# oresat-camera-board-v2.net
KiCad netlist of a schematic drawn in EAGLE
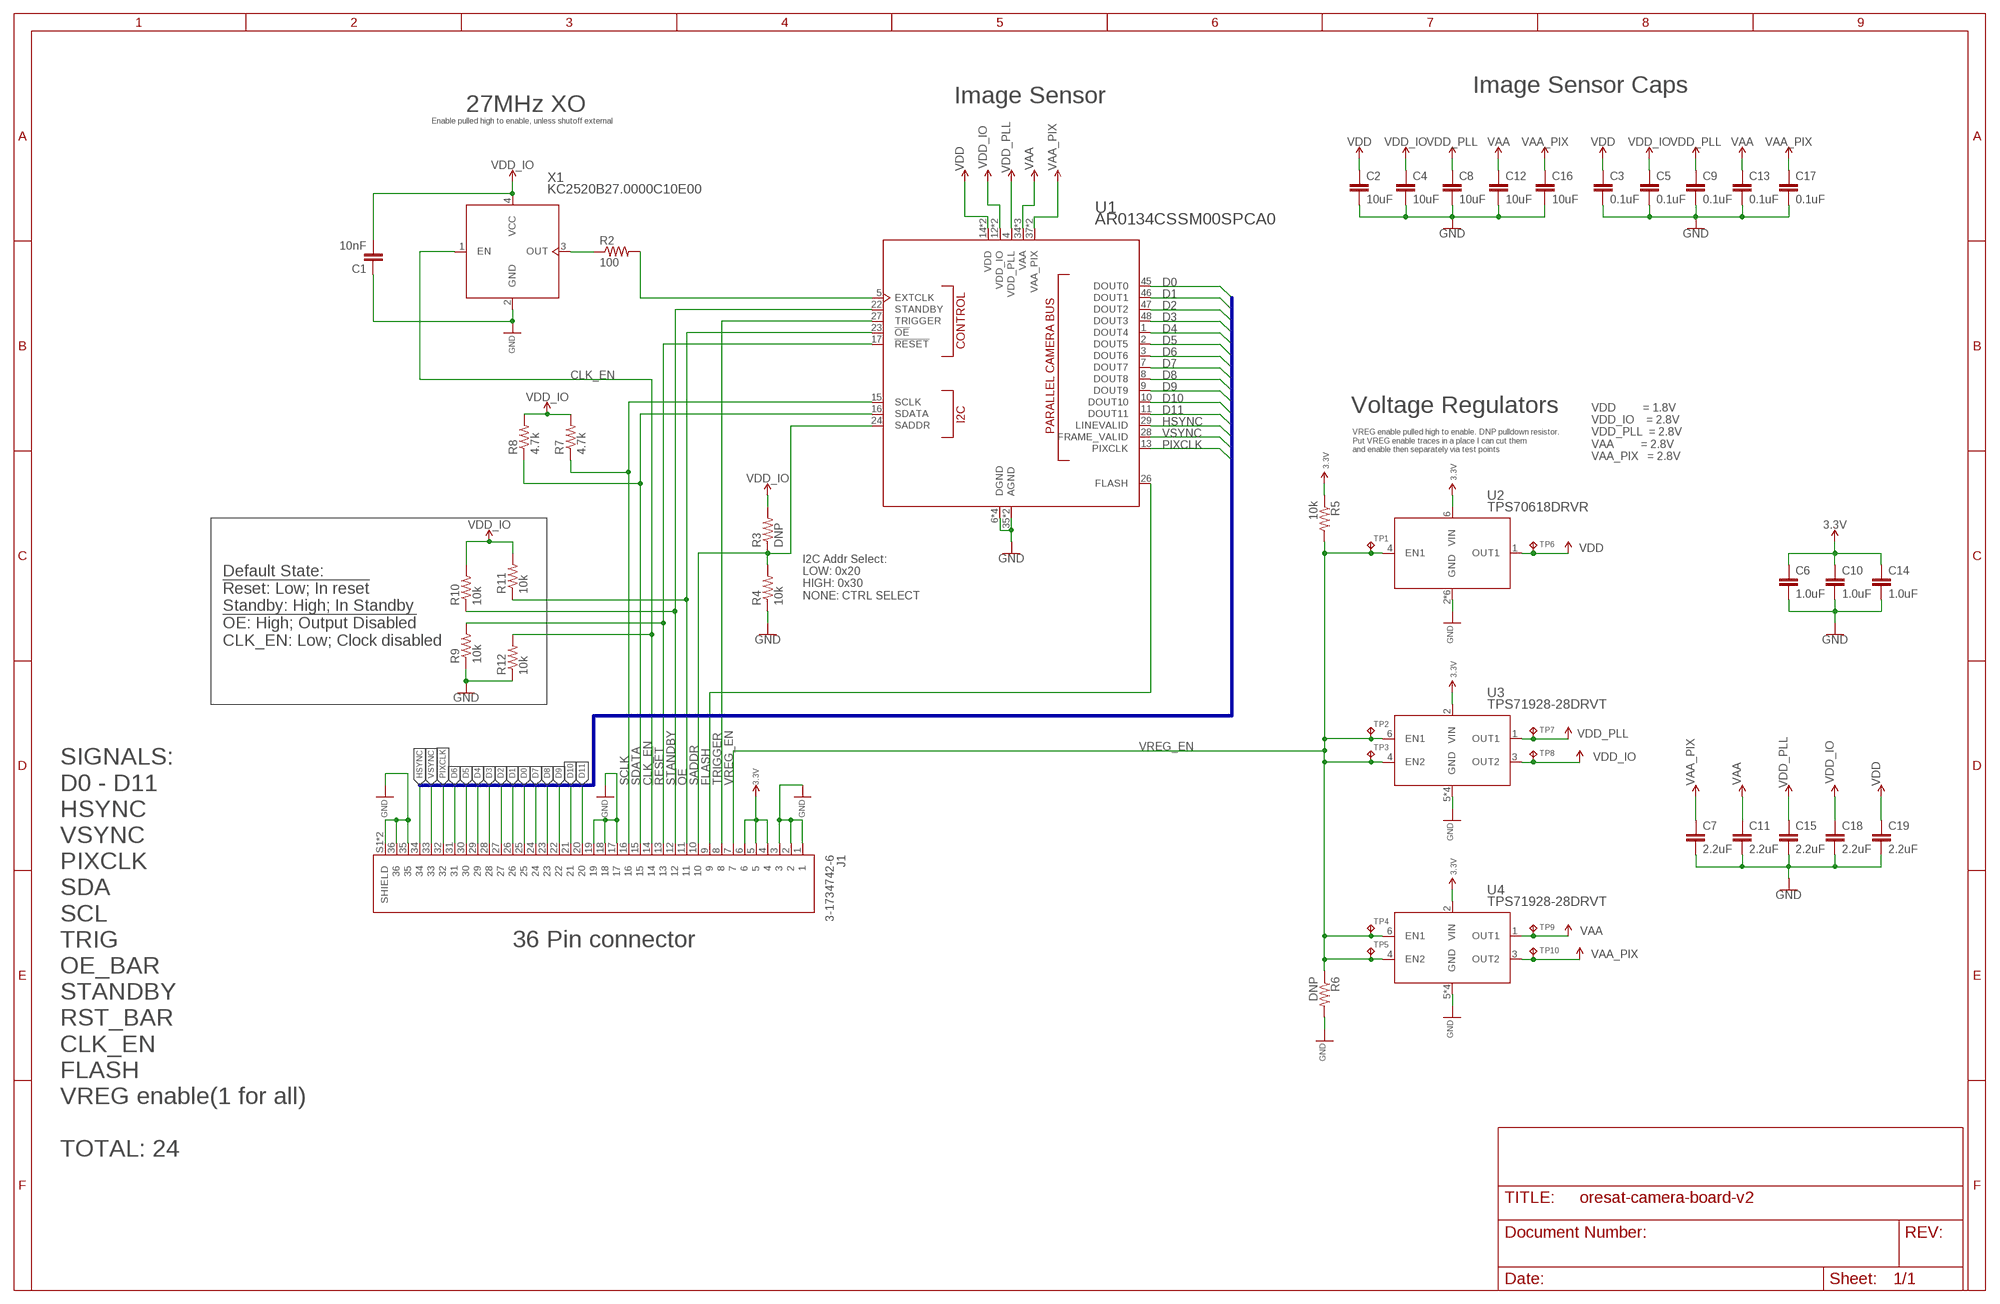
[diagram p0: schematic, sheet 1]

(export (version "E")
  (design (tool "Eeschema 10.0.6"))
  (components
    (comp (ref "C1")
      (value "10nF")
      (footprint "eagle-import:.0402-A-NOSILK")
      (libsource (lib "eagle-import") (part "C-EU0402-A-NOSILK"))
    )
    (comp (ref "C2")
      (value "10uF")
      (footprint "eagle-import:.0603-C-NOSILK")
      (libsource (lib "eagle-import") (part "C-EU0603-C-NOSILK"))
    )
    (comp (ref "C3")
      (value "0.1uF")
      (footprint "eagle-import:.0402-B-NOSILK")
      (libsource (lib "eagle-import") (part "C-EU0402-B-NOSILK"))
    )
    (comp (ref "C4")
      (value "10uF")
      (footprint "eagle-import:.0603-C-NOSILK")
      (libsource (lib "eagle-import") (part "C-EU0603-C-NOSILK"))
    )
    (comp (ref "C5")
      (value "0.1uF")
      (footprint "eagle-import:.0402-B-NOSILK")
      (libsource (lib "eagle-import") (part "C-EU0402-B-NOSILK"))
    )
    (comp (ref "C6")
      (value "1.0uF")
      (footprint "eagle-import:.0603-C-NOSILK")
      (libsource (lib "eagle-import") (part "C-EU0603-C-NOSILK"))
    )
    (comp (ref "C7")
      (value "2.2uF")
      (footprint "eagle-import:.0603-C-NOSILK")
      (libsource (lib "eagle-import") (part "C-EU0603-C-NOSILK"))
    )
    (comp (ref "C8")
      (value "10uF")
      (footprint "eagle-import:.0603-C-NOSILK")
      (libsource (lib "eagle-import") (part "C-EU0603-C-NOSILK"))
    )
    (comp (ref "C9")
      (value "0.1uF")
      (footprint "eagle-import:.0402-B-NOSILK")
      (libsource (lib "eagle-import") (part "C-EU0402-B-NOSILK"))
    )
    (comp (ref "C10")
      (value "1.0uF")
      (footprint "eagle-import:.0603-C-NOSILK")
      (libsource (lib "eagle-import") (part "C-EU0603-C-NOSILK"))
    )
    (comp (ref "C11")
      (value "2.2uF")
      (footprint "eagle-import:.0603-C-NOSILK")
      (libsource (lib "eagle-import") (part "C-EU0603-C-NOSILK"))
    )
    (comp (ref "C12")
      (value "10uF")
      (footprint "eagle-import:.0603-C-NOSILK")
      (libsource (lib "eagle-import") (part "C-EU0603-C-NOSILK"))
    )
    (comp (ref "C13")
      (value "0.1uF")
      (footprint "eagle-import:.0402-B-NOSILK")
      (libsource (lib "eagle-import") (part "C-EU0402-B-NOSILK"))
    )
    (comp (ref "C14")
      (value "1.0uF")
      (footprint "eagle-import:.0603-C-NOSILK")
      (libsource (lib "eagle-import") (part "C-EU0603-C-NOSILK"))
    )
    (comp (ref "C15")
      (value "2.2uF")
      (footprint "eagle-import:.0603-C-NOSILK")
      (libsource (lib "eagle-import") (part "C-EU0603-C-NOSILK"))
    )
    (comp (ref "C16")
      (value "10uF")
      (footprint "eagle-import:.0603-C-NOSILK")
      (libsource (lib "eagle-import") (part "C-EU0603-C-NOSILK"))
    )
    (comp (ref "C17")
      (value "0.1uF")
      (footprint "eagle-import:.0402-B-NOSILK")
      (libsource (lib "eagle-import") (part "C-EU0402-B-NOSILK"))
    )
    (comp (ref "C18")
      (value "2.2uF")
      (footprint "eagle-import:.0603-C-NOSILK")
      (libsource (lib "eagle-import") (part "C-EU0603-C-NOSILK"))
    )
    (comp (ref "C19")
      (value "2.2uF")
      (footprint "eagle-import:.0603-C-NOSILK")
      (libsource (lib "eagle-import") (part "C-EU0603-C-NOSILK"))
    )
    (comp (ref "J1")
      (value "3-1734742-6")
      (footprint "eagle-import:TE_3-1734742-6")
      (fields
        (field (name "COMMENT") "4-1734742-0")
        (field (name "DIGI-KEY_PART_NUMBER") "A100242CT-ND")
        (field (name "MF") "TE Connectivity")
      )
      (libsource (lib "eagle-import") (part "3-1734742-6"))
    )
    (comp (ref "R2")
      (value "100")
      (footprint "eagle-import:.0402-B")
      (libsource (lib "eagle-import") (part "R-US_0402-B"))
    )
    (comp (ref "R3")
      (value "DNP")
      (footprint "eagle-import:.0402-B-NOSILK")
      (libsource (lib "eagle-import") (part "R-US_0402-B-NOSILK"))
    )
    (comp (ref "R4")
      (value "10k")
      (footprint "eagle-import:.0402-B-NOSILK")
      (libsource (lib "eagle-import") (part "R-US_0402-B-NOSILK"))
    )
    (comp (ref "R5")
      (value "10k")
      (footprint "eagle-import:.0402-B-NOSILK")
      (libsource (lib "eagle-import") (part "R-US_0402-B-NOSILK"))
    )
    (comp (ref "R6")
      (value "DNP")
      (footprint "eagle-import:.0402-B-NOSILK")
      (libsource (lib "eagle-import") (part "R-US_0402-B-NOSILK"))
    )
    (comp (ref "R7")
      (value "4.7k")
      (footprint "eagle-import:.0402-B-NOSILK")
      (libsource (lib "eagle-import") (part "R-US_0402-B-NOSILK"))
    )
    (comp (ref "R8")
      (value "4.7k")
      (footprint "eagle-import:.0402-B-NOSILK")
      (libsource (lib "eagle-import") (part "R-US_0402-B-NOSILK"))
    )
    (comp (ref "R9")
      (value "10k")
      (footprint "eagle-import:.0402-B")
      (libsource (lib "eagle-import") (part "R-US_0402-B"))
    )
    (comp (ref "R10")
      (value "10k")
      (footprint "eagle-import:.0402-B")
      (libsource (lib "eagle-import") (part "R-US_0402-B"))
    )
    (comp (ref "R11")
      (value "10k")
      (footprint "eagle-import:.0402-B")
      (libsource (lib "eagle-import") (part "R-US_0402-B"))
    )
    (comp (ref "R12")
      (value "10k")
      (footprint "eagle-import:.0402-B")
      (libsource (lib "eagle-import") (part "R-US_0402-B"))
    )
    (comp (ref "TP1")
      (value "TPTP06R")
      (footprint "eagle-import:TP06R")
      (libsource (lib "eagle-import") (part "TPTP06R"))
    )
    (comp (ref "TP2")
      (value "TPTP06R")
      (footprint "eagle-import:TP06R")
      (libsource (lib "eagle-import") (part "TPTP06R"))
    )
    (comp (ref "TP3")
      (value "TPTP06R")
      (footprint "eagle-import:TP06R")
      (libsource (lib "eagle-import") (part "TPTP06R"))
    )
    (comp (ref "TP4")
      (value "TPTP06R")
      (footprint "eagle-import:TP06R")
      (libsource (lib "eagle-import") (part "TPTP06R"))
    )
    (comp (ref "TP5")
      (value "TPTP06R")
      (footprint "eagle-import:TP06R")
      (libsource (lib "eagle-import") (part "TPTP06R"))
    )
    (comp (ref "TP6")
      (value "TPTP06R")
      (footprint "eagle-import:TP06R")
      (libsource (lib "eagle-import") (part "TPTP06R"))
    )
    (comp (ref "TP7")
      (value "TPTP06R")
      (footprint "eagle-import:TP06R")
      (libsource (lib "eagle-import") (part "TPTP06R"))
    )
    (comp (ref "TP8")
      (value "TPTP06R")
      (footprint "eagle-import:TP06R")
      (libsource (lib "eagle-import") (part "TPTP06R"))
    )
    (comp (ref "TP9")
      (value "TPTP06R")
      (footprint "eagle-import:TP06R")
      (libsource (lib "eagle-import") (part "TPTP06R"))
    )
    (comp (ref "TP10")
      (value "TPTP06R")
      (footprint "eagle-import:TP06R")
      (libsource (lib "eagle-import") (part "TPTP06R"))
    )
    (comp (ref "U1")
      (value "AR0134CSSM00SPCA0")
      (footprint "eagle-import:AR0134CSSM00SPCA0")
      (libsource (lib "eagle-import") (part "AR0134CSSM00SPCA0"))
    )
    (comp (ref "U2")
      (value "TPS70618DRVR")
      (footprint "eagle-import:DRV6_1P6X1")
      (fields (field (name "MANUFACTURER_PART_NUMBER") "TPS7192828DRVT"))
      (libsource (lib "eagle-import") (part "TPS70618DRVR"))
    )
    (comp (ref "U3")
      (value "TPS71928-28DRVT")
      (footprint "eagle-import:DRV6_1P6X1")
      (fields (field (name "MANUFACTURER_PART_NUMBER") "TPS7192828DRVT"))
      (libsource (lib "eagle-import") (part "TPS71928-28DRVT"))
    )
    (comp (ref "U4")
      (value "TPS71928-28DRVT")
      (footprint "eagle-import:DRV6_1P6X1")
      (fields (field (name "MANUFACTURER_PART_NUMBER") "TPS7192828DRVT"))
      (libsource (lib "eagle-import") (part "TPS71928-28DRVT"))
    )
    (comp (ref "X1")
      (value "KC2520B27.0000C10E00")
      (footprint "eagle-import:OSC_KYOCERA_KC2520B")
      (libsource (lib "eagle-import") (part "KC2520B27.0000C10E00"))
    )
  )
  (nets
    (net (code "1") (name "/CLK_EN") (class "Default")
      (node (ref "J1") (pin "14") (pinfunction "14_14") (pintype "passive"))
      (node (ref "R12") (pin "2") (pinfunction "2_2") (pintype "passive"))
      (node (ref "X1") (pin "1") (pinfunction "EN_1") (pintype "passive"))
    )
    (net (code "2") (name "/FLASH") (class "Default")
      (node (ref "J1") (pin "9") (pinfunction "9_9") (pintype "passive"))
      (node (ref "U1") (pin "26") (pinfunction "FLASH_26") (pintype "bidirectional"))
    )
    (net (code "3") (name "/SADDR") (class "Default")
      (node (ref "J1") (pin "10") (pinfunction "10_10") (pintype "passive"))
      (node (ref "R3") (pin "1") (pinfunction "1_1") (pintype "passive"))
      (node (ref "R4") (pin "2") (pinfunction "2_2") (pintype "passive"))
      (node (ref "U1") (pin "24") (pinfunction "SADDR_24") (pintype "bidirectional"))
    )
    (net (code "4") (name "/SCLK") (class "Default")
      (node (ref "J1") (pin "16") (pinfunction "16_16") (pintype "passive"))
      (node (ref "R7") (pin "1") (pinfunction "1_1") (pintype "passive"))
      (node (ref "U1") (pin "15") (pinfunction "SCLK_15") (pintype "bidirectional"))
    )
    (net (code "5") (name "/SDATA") (class "Default")
      (node (ref "J1") (pin "15") (pinfunction "15_15") (pintype "passive"))
      (node (ref "R8") (pin "1") (pinfunction "1_1") (pintype "passive"))
      (node (ref "U1") (pin "16") (pinfunction "SDATA_16") (pintype "bidirectional"))
    )
    (net (code "6") (name "/STANDBY") (class "Default")
      (node (ref "J1") (pin "12") (pinfunction "12_12") (pintype "passive"))
      (node (ref "R10") (pin "1") (pinfunction "1_1") (pintype "passive"))
      (node (ref "U1") (pin "22") (pinfunction "STANDBY_22") (pintype "bidirectional"))
    )
    (net (code "7") (name "/TRIGGER") (class "Default")
      (node (ref "J1") (pin "8") (pinfunction "8_8") (pintype "passive"))
      (node (ref "U1") (pin "27") (pinfunction "TRIGGER_27") (pintype "bidirectional"))
    )
    (net (code "8") (name "/VREG_EN") (class "Default")
      (node (ref "J1") (pin "7") (pinfunction "7_7") (pintype "passive"))
      (node (ref "R5") (pin "2") (pinfunction "2_2") (pintype "passive"))
      (node (ref "R6") (pin "1") (pinfunction "1_1") (pintype "passive"))
      (node (ref "TP1") (pin "TP") (pinfunction "TP_TP") (pintype "input"))
      (node (ref "TP2") (pin "TP") (pinfunction "TP_TP") (pintype "input"))
      (node (ref "TP3") (pin "TP") (pinfunction "TP_TP") (pintype "input"))
      (node (ref "TP4") (pin "TP") (pinfunction "TP_TP") (pintype "input"))
      (node (ref "TP5") (pin "TP") (pinfunction "TP_TP") (pintype "input"))
      (node (ref "U2") (pin "4") (pinfunction "EN1_4") (pintype "passive"))
      (node (ref "U3") (pin "4") (pinfunction "EN2_4") (pintype "passive"))
      (node (ref "U3") (pin "6") (pinfunction "EN1_6") (pintype "passive"))
      (node (ref "U4") (pin "4") (pinfunction "EN2_4") (pintype "passive"))
      (node (ref "U4") (pin "6") (pinfunction "EN1_6") (pintype "passive"))
    )
    (net (code "9") (name "/~{OE}") (class "Default")
      (node (ref "J1") (pin "11") (pinfunction "11_11") (pintype "passive"))
      (node (ref "R11") (pin "1") (pinfunction "1_1") (pintype "passive"))
      (node (ref "U1") (pin "23") (pinfunction "~{OE}_23") (pintype "bidirectional"))
    )
    (net (code "10") (name "/~{RESET}") (class "Default")
      (node (ref "J1") (pin "13") (pinfunction "13_13") (pintype "passive"))
      (node (ref "R9") (pin "2") (pinfunction "2_2") (pintype "passive"))
      (node (ref "U1") (pin "17") (pinfunction "~{RESET}_17") (pintype "bidirectional"))
    )
    (net (code "11") (name "3.3V") (class "Default")
      (node (ref "C10") (pin "1") (pinfunction "1_1") (pintype "passive"))
      (node (ref "C14") (pin "1") (pinfunction "1_1") (pintype "passive"))
      (node (ref "C6") (pin "1") (pinfunction "1_1") (pintype "passive"))
      (node (ref "J1") (pin "4") (pinfunction "4_4") (pintype "passive"))
      (node (ref "J1") (pin "5") (pinfunction "5_5") (pintype "passive"))
      (node (ref "J1") (pin "6") (pinfunction "6_6") (pintype "passive"))
      (node (ref "R5") (pin "1") (pinfunction "1_1") (pintype "passive"))
      (node (ref "U2") (pin "6") (pinfunction "VIN_6") (pintype "input"))
      (node (ref "U3") (pin "2") (pinfunction "VIN_2") (pintype "power_in"))
      (node (ref "U4") (pin "2") (pinfunction "VIN_2") (pintype "power_in"))
    )
    (net (code "12") (name "D0") (class "Default")
      (node (ref "J1") (pin "25") (pinfunction "25_25") (pintype "passive"))
      (node (ref "U1") (pin "45") (pinfunction "DOUT0_45") (pintype "bidirectional"))
    )
    (net (code "13") (name "D1") (class "Default")
      (node (ref "J1") (pin "26") (pinfunction "26_26") (pintype "passive"))
      (node (ref "U1") (pin "46") (pinfunction "DOUT1_46") (pintype "bidirectional"))
    )
    (net (code "14") (name "D2") (class "Default")
      (node (ref "J1") (pin "27") (pinfunction "27_27") (pintype "passive"))
      (node (ref "U1") (pin "47") (pinfunction "DOUT2_47") (pintype "bidirectional"))
    )
    (net (code "15") (name "D3") (class "Default")
      (node (ref "J1") (pin "28") (pinfunction "28_28") (pintype "passive"))
      (node (ref "U1") (pin "48") (pinfunction "DOUT3_48") (pintype "bidirectional"))
    )
    (net (code "16") (name "D4") (class "Default")
      (node (ref "J1") (pin "29") (pinfunction "29_29") (pintype "passive"))
      (node (ref "U1") (pin "1") (pinfunction "DOUT4_1") (pintype "bidirectional"))
    )
    (net (code "17") (name "D5") (class "Default")
      (node (ref "J1") (pin "30") (pinfunction "30_30") (pintype "passive"))
      (node (ref "U1") (pin "2") (pinfunction "DOUT5_2") (pintype "bidirectional"))
    )
    (net (code "18") (name "D6") (class "Default")
      (node (ref "J1") (pin "31") (pinfunction "31_31") (pintype "passive"))
      (node (ref "U1") (pin "3") (pinfunction "DOUT6_3") (pintype "bidirectional"))
    )
    (net (code "19") (name "D7") (class "Default")
      (node (ref "J1") (pin "24") (pinfunction "24_24") (pintype "passive"))
      (node (ref "U1") (pin "7") (pinfunction "DOUT7_7") (pintype "bidirectional"))
    )
    (net (code "20") (name "D8") (class "Default")
      (node (ref "J1") (pin "23") (pinfunction "23_23") (pintype "passive"))
      (node (ref "U1") (pin "8") (pinfunction "DOUT8_8") (pintype "bidirectional"))
    )
    (net (code "21") (name "D9") (class "Default")
      (node (ref "J1") (pin "22") (pinfunction "22_22") (pintype "passive"))
      (node (ref "U1") (pin "9") (pinfunction "DOUT9_9") (pintype "bidirectional"))
    )
    (net (code "22") (name "D10") (class "Default")
      (node (ref "J1") (pin "21") (pinfunction "21_21") (pintype "passive"))
      (node (ref "U1") (pin "10") (pinfunction "DOUT10_10") (pintype "bidirectional"))
    )
    (net (code "23") (name "D11") (class "Default")
      (node (ref "J1") (pin "20") (pinfunction "20_20") (pintype "passive"))
      (node (ref "U1") (pin "11") (pinfunction "DOUT11_11") (pintype "bidirectional"))
    )
    (net (code "24") (name "GND") (class "Default")
      (node (ref "C1") (pin "1") (pinfunction "1_1") (pintype "passive"))
      (node (ref "C10") (pin "2") (pinfunction "2_2") (pintype "passive"))
      (node (ref "C11") (pin "2") (pinfunction "2_2") (pintype "passive"))
      (node (ref "C12") (pin "2") (pinfunction "2_2") (pintype "passive"))
      (node (ref "C13") (pin "2") (pinfunction "2_2") (pintype "passive"))
      (node (ref "C14") (pin "2") (pinfunction "2_2") (pintype "passive"))
      (node (ref "C15") (pin "2") (pinfunction "2_2") (pintype "passive"))
      (node (ref "C16") (pin "2") (pinfunction "2_2") (pintype "passive"))
      (node (ref "C17") (pin "2") (pinfunction "2_2") (pintype "passive"))
      (node (ref "C18") (pin "2") (pinfunction "2_2") (pintype "passive"))
      (node (ref "C19") (pin "2") (pinfunction "2_2") (pintype "passive"))
      (node (ref "C2") (pin "2") (pinfunction "2_2") (pintype "passive"))
      (node (ref "C3") (pin "2") (pinfunction "2_2") (pintype "passive"))
      (node (ref "C4") (pin "2") (pinfunction "2_2") (pintype "passive"))
      (node (ref "C5") (pin "2") (pinfunction "2_2") (pintype "passive"))
      (node (ref "C6") (pin "2") (pinfunction "2_2") (pintype "passive"))
      (node (ref "C7") (pin "2") (pinfunction "2_2") (pintype "passive"))
      (node (ref "C8") (pin "2") (pinfunction "2_2") (pintype "passive"))
      (node (ref "C9") (pin "2") (pinfunction "2_2") (pintype "passive"))
      (node (ref "J1") (pin "1") (pinfunction "1_1") (pintype "passive"))
      (node (ref "J1") (pin "17") (pinfunction "17_17") (pintype "passive"))
      (node (ref "J1") (pin "18") (pinfunction "18_18") (pintype "passive"))
      (node (ref "J1") (pin "19") (pinfunction "19_19") (pintype "passive"))
      (node (ref "J1") (pin "2") (pinfunction "2_2") (pintype "passive"))
      (node (ref "J1") (pin "3") (pinfunction "3_3") (pintype "passive"))
      (node (ref "J1") (pin "35") (pinfunction "35_35") (pintype "passive"))
      (node (ref "J1") (pin "36") (pinfunction "36_36") (pintype "passive"))
      (node (ref "J1") (pin "S1") (pinfunction "SHIELD_S1") (pintype "passive"))
      (node (ref "J1") (pin "S2") (pinfunction "SHIELD_S2") (pintype "passive"))
      (node (ref "R12") (pin "1") (pinfunction "1_1") (pintype "passive"))
      (node (ref "R4") (pin "1") (pinfunction "1_1") (pintype "passive"))
      (node (ref "R6") (pin "2") (pinfunction "2_2") (pintype "passive"))
      (node (ref "R9") (pin "1") (pinfunction "1_1") (pintype "passive"))
      (node (ref "U1") (pin "25") (pinfunction "DGND_25") (pintype "power_in"))
      (node (ref "U1") (pin "30") (pinfunction "DGND_30") (pintype "power_in"))
      (node (ref "U1") (pin "35") (pinfunction "AGND_35") (pintype "power_in"))
      (node (ref "U1") (pin "39") (pinfunction "AGND_39") (pintype "power_in"))
      (node (ref "U1") (pin "44") (pinfunction "DGND_44") (pintype "power_in"))
      (node (ref "U1") (pin "6") (pinfunction "DGND_6") (pintype "power_in"))
      (node (ref "U2") (pin "2") (pinfunction "GND_2") (pintype "power_in"))
      (node (ref "U2") (pin "3") (pinfunction "GND_3") (pintype "power_in"))
      (node (ref "U2") (pin "5") (pinfunction "GND_5") (pintype "power_in"))
      (node (ref "U2") (pin "7") (pinfunction "GND_7") (pintype "power_in"))
      (node (ref "U2") (pin "8") (pinfunction "GND_8") (pintype "power_in"))
      (node (ref "U2") (pin "9") (pinfunction "GND_9") (pintype "power_in"))
      (node (ref "U3") (pin "5") (pinfunction "GND_5") (pintype "power_in"))
      (node (ref "U3") (pin "7") (pinfunction "GND_7") (pintype "power_in"))
      (node (ref "U3") (pin "8") (pinfunction "GND_8") (pintype "power_in"))
      (node (ref "U3") (pin "9") (pinfunction "GND_9") (pintype "power_in"))
      (node (ref "U4") (pin "5") (pinfunction "GND_5") (pintype "power_in"))
      (node (ref "U4") (pin "7") (pinfunction "GND_7") (pintype "power_in"))
      (node (ref "U4") (pin "8") (pinfunction "GND_8") (pintype "power_in"))
      (node (ref "U4") (pin "9") (pinfunction "GND_9") (pintype "power_in"))
      (node (ref "X1") (pin "2") (pinfunction "GND_2") (pintype "power_in"))
    )
    (net (code "25") (name "HSYNC") (class "Default")
      (node (ref "J1") (pin "34") (pinfunction "34_34") (pintype "passive"))
      (node (ref "U1") (pin "29") (pinfunction "LINEVALID_29") (pintype "bidirectional"))
    )
    (net (code "26") (name "Net-(U1-EXTCLK)") (class "Default")
      (node (ref "R2") (pin "2") (pinfunction "2_2") (pintype "passive"))
      (node (ref "U1") (pin "5") (pinfunction "EXTCLK_5") (pintype "bidirectional"))
    )
    (net (code "27") (name "Net-(X1-OUT)") (class "Default")
      (node (ref "R2") (pin "1") (pinfunction "1_1") (pintype "passive"))
      (node (ref "X1") (pin "3") (pinfunction "OUT_3") (pintype "output"))
    )
    (net (code "28") (name "PIXCLK") (class "Default")
      (node (ref "J1") (pin "32") (pinfunction "32_32") (pintype "passive"))
      (node (ref "U1") (pin "13") (pinfunction "PIXCLK_13") (pintype "bidirectional"))
    )
    (net (code "29") (name "VAA") (class "Default")
      (node (ref "C11") (pin "1") (pinfunction "1_1") (pintype "passive"))
      (node (ref "C12") (pin "1") (pinfunction "1_1") (pintype "passive"))
      (node (ref "C13") (pin "1") (pinfunction "1_1") (pintype "passive"))
      (node (ref "TP9") (pin "TP") (pinfunction "TP_TP") (pintype "input"))
      (node (ref "U1") (pin "34") (pinfunction "VAA_34") (pintype "power_in"))
      (node (ref "U1") (pin "36") (pinfunction "VAA_36") (pintype "power_in"))
      (node (ref "U1") (pin "40") (pinfunction "VAA_40") (pintype "power_in"))
      (node (ref "U4") (pin "1") (pinfunction "OUT1_1") (pintype "power_in"))
    )
    (net (code "30") (name "VAA_PIX") (class "Default")
      (node (ref "C16") (pin "1") (pinfunction "1_1") (pintype "passive"))
      (node (ref "C17") (pin "1") (pinfunction "1_1") (pintype "passive"))
      (node (ref "C7") (pin "1") (pinfunction "1_1") (pintype "passive"))
      (node (ref "TP10") (pin "TP") (pinfunction "TP_TP") (pintype "input"))
      (node (ref "U1") (pin "37") (pinfunction "VAA_PIX_37") (pintype "power_in"))
      (node (ref "U1") (pin "38") (pinfunction "VAA_PIX_38") (pintype "power_in"))
      (node (ref "U4") (pin "3") (pinfunction "OUT2_3") (pintype "power_in"))
    )
    (net (code "31") (name "VDD") (class "Default")
      (node (ref "C19") (pin "1") (pinfunction "1_1") (pintype "passive"))
      (node (ref "C2") (pin "1") (pinfunction "1_1") (pintype "passive"))
      (node (ref "C3") (pin "1") (pinfunction "1_1") (pintype "passive"))
      (node (ref "TP6") (pin "TP") (pinfunction "TP_TP") (pintype "input"))
      (node (ref "U1") (pin "14") (pinfunction "VDD_14") (pintype "power_in"))
      (node (ref "U1") (pin "19") (pinfunction "VDD_19") (pintype "power_in"))
      (node (ref "U2") (pin "1") (pinfunction "OUT1_1") (pintype "passive"))
    )
    (net (code "32") (name "VDD_IO") (class "Default")
      (node (ref "C1") (pin "2") (pinfunction "2_2") (pintype "passive"))
      (node (ref "C18") (pin "1") (pinfunction "1_1") (pintype "passive"))
      (node (ref "C4") (pin "1") (pinfunction "1_1") (pintype "passive"))
      (node (ref "C5") (pin "1") (pinfunction "1_1") (pintype "passive"))
      (node (ref "R10") (pin "2") (pinfunction "2_2") (pintype "passive"))
      (node (ref "R11") (pin "2") (pinfunction "2_2") (pintype "passive"))
      (node (ref "R3") (pin "2") (pinfunction "2_2") (pintype "passive"))
      (node (ref "R7") (pin "2") (pinfunction "2_2") (pintype "passive"))
      (node (ref "R8") (pin "2") (pinfunction "2_2") (pintype "passive"))
      (node (ref "TP8") (pin "TP") (pinfunction "TP_TP") (pintype "input"))
      (node (ref "U1") (pin "12") (pinfunction "VDD_IO_12") (pintype "power_in"))
      (node (ref "U1") (pin "18") (pinfunction "VDD_IO_18") (pintype "power_in"))
      (node (ref "U3") (pin "3") (pinfunction "OUT2_3") (pintype "power_in"))
      (node (ref "X1") (pin "4") (pinfunction "VCC_4") (pintype "power_in"))
    )
    (net (code "33") (name "VDD_PLL") (class "Default")
      (node (ref "C15") (pin "1") (pinfunction "1_1") (pintype "passive"))
      (node (ref "C8") (pin "1") (pinfunction "1_1") (pintype "passive"))
      (node (ref "C9") (pin "1") (pinfunction "1_1") (pintype "passive"))
      (node (ref "TP7") (pin "TP") (pinfunction "TP_TP") (pintype "input"))
      (node (ref "U1") (pin "4") (pinfunction "VDD_PLL_4") (pintype "power_in"))
      (node (ref "U3") (pin "1") (pinfunction "OUT1_1") (pintype "power_in"))
    )
    (net (code "34") (name "VSYNC") (class "Default")
      (node (ref "J1") (pin "33") (pinfunction "33_33") (pintype "passive"))
      (node (ref "U1") (pin "28") (pinfunction "FRAME_VALID_28") (pintype "bidirectional"))
    )
  )
)
